# macropad_versio2.net
KiCad netlist of a schematic drawn in EAGLE
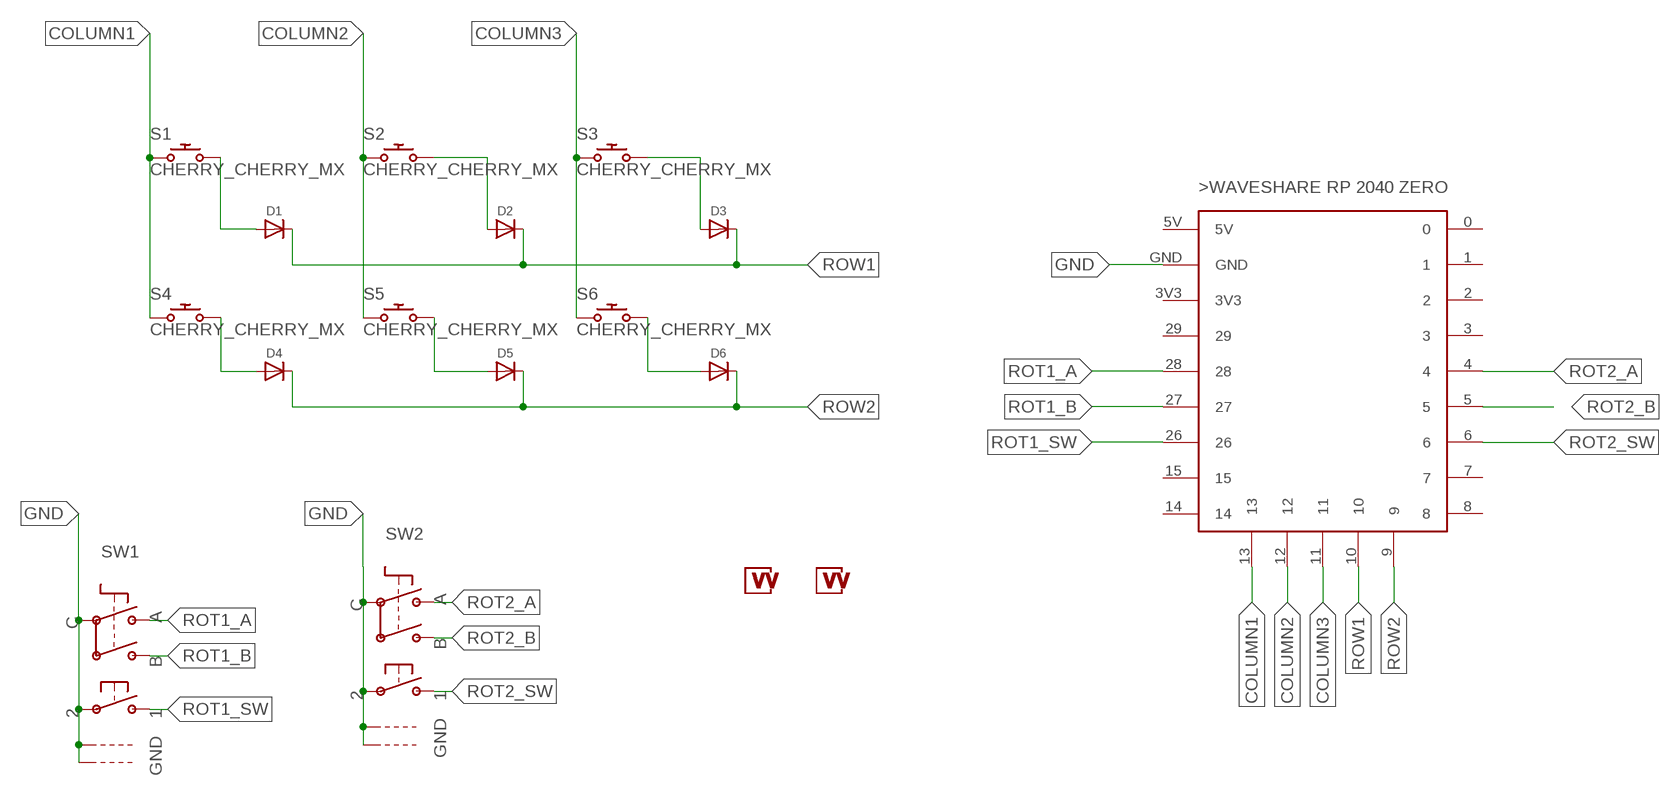
[diagram p0: schematic, sheet 1]

(export (version "E")
  (design (tool "Eeschema 10.0.6"))
  (components
    (comp (ref "D1")
      (value "ADAFRUIT-MACROPAD-2040_MICROBUILDER_DIODESOD-123")
      (footprint "eagle-import:ADAFRUIT-MACROPAD-2040_MICROBUILDER_SOD-123")
      (libsource (lib "eagle-import") (part "ADAFRUIT-MACROPAD-2040_MICROBUILDER_DIODESOD-123"))
    )
    (comp (ref "D2")
      (value "ADAFRUIT-MACROPAD-2040_MICROBUILDER_DIODESOD-123")
      (footprint "eagle-import:ADAFRUIT-MACROPAD-2040_MICROBUILDER_SOD-123")
      (libsource (lib "eagle-import") (part "ADAFRUIT-MACROPAD-2040_MICROBUILDER_DIODESOD-123"))
    )
    (comp (ref "D3")
      (value "ADAFRUIT-MACROPAD-2040_MICROBUILDER_DIODESOD-123")
      (footprint "eagle-import:ADAFRUIT-MACROPAD-2040_MICROBUILDER_SOD-123")
      (libsource (lib "eagle-import") (part "ADAFRUIT-MACROPAD-2040_MICROBUILDER_DIODESOD-123"))
    )
    (comp (ref "D4")
      (value "ADAFRUIT-MACROPAD-2040_MICROBUILDER_DIODESOD-123")
      (footprint "eagle-import:ADAFRUIT-MACROPAD-2040_MICROBUILDER_SOD-123")
      (libsource (lib "eagle-import") (part "ADAFRUIT-MACROPAD-2040_MICROBUILDER_DIODESOD-123"))
    )
    (comp (ref "D5")
      (value "ADAFRUIT-MACROPAD-2040_MICROBUILDER_DIODESOD-123")
      (footprint "eagle-import:ADAFRUIT-MACROPAD-2040_MICROBUILDER_SOD-123")
      (libsource (lib "eagle-import") (part "ADAFRUIT-MACROPAD-2040_MICROBUILDER_DIODESOD-123"))
    )
    (comp (ref "D6")
      (value "ADAFRUIT-MACROPAD-2040_MICROBUILDER_DIODESOD-123")
      (footprint "eagle-import:ADAFRUIT-MACROPAD-2040_MICROBUILDER_SOD-123")
      (libsource (lib "eagle-import") (part "ADAFRUIT-MACROPAD-2040_MICROBUILDER_DIODESOD-123"))
    )
    (comp (ref "RP2040_ZERO1")
      (value "WAVESHARE_RP2040_ZERO")
      (footprint "eagle-import:WAVESHARE-RP2040-ZERO")
      (libsource (lib "eagle-import") (part "WAVESHARE_RP2040_ZERO"))
    )
    (comp (ref "S1")
      (value "CHERRY_CHERRY_MX")
      (footprint "eagle-import:CHERRY_CHERRY_MX")
      (libsource (lib "eagle-import") (part "CHERRY_CHERRY_MX"))
    )
    (comp (ref "S2")
      (value "CHERRY_CHERRY_MX")
      (footprint "eagle-import:CHERRY_CHERRY_MX")
      (libsource (lib "eagle-import") (part "CHERRY_CHERRY_MX"))
    )
    (comp (ref "S3")
      (value "CHERRY_CHERRY_MX")
      (footprint "eagle-import:CHERRY_CHERRY_MX")
      (libsource (lib "eagle-import") (part "CHERRY_CHERRY_MX"))
    )
    (comp (ref "S4")
      (value "CHERRY_CHERRY_MX")
      (footprint "eagle-import:CHERRY_CHERRY_MX")
      (libsource (lib "eagle-import") (part "CHERRY_CHERRY_MX"))
    )
    (comp (ref "S5")
      (value "CHERRY_CHERRY_MX")
      (footprint "eagle-import:CHERRY_CHERRY_MX")
      (libsource (lib "eagle-import") (part "CHERRY_CHERRY_MX"))
    )
    (comp (ref "S6")
      (value "CHERRY_CHERRY_MX")
      (footprint "eagle-import:CHERRY_CHERRY_MX")
      (libsource (lib "eagle-import") (part "CHERRY_CHERRY_MX"))
    )
    (comp (ref "SW1")
      (value "ADAFRUIT-MACROPAD-2040_ADAFRUIT_ELECTROMECH_ENCODER_PLUS_SWITCH_BOURNS_PEC11")
      (footprint "eagle-import:ADAFRUIT-MACROPAD-2040_ADAFRUIT_ELECTROMECH_PEC11+SWITCH")
      (libsource (lib "eagle-import") (part "ADAFRUIT-MACROPAD-2040_ADAFRUIT_ELECTROMECH_ENCODER_PLUS_SWITCH_PEC11_BOURNS"))
    )
    (comp (ref "SW2")
      (value "ADAFRUIT-MACROPAD-2040_ADAFRUIT_ELECTROMECH_ENCODER_PLUS_SWITCH_BOURNS_PEC11")
      (footprint "eagle-import:ADAFRUIT-MACROPAD-2040_ADAFRUIT_ELECTROMECH_PEC11+SWITCH")
      (libsource (lib "eagle-import") (part "ADAFRUIT-MACROPAD-2040_ADAFRUIT_ELECTROMECH_ENCODER_PLUS_SWITCH_PEC11_BOURNS"))
    )
    (comp (ref "U$1")
      (value "LOGO_VV")
      (footprint "eagle-import:VV_MEDUIM")
      (libsource (lib "eagle-import") (part "LOGO_VV"))
    )
    (comp (ref "U$2")
      (value "LOGO_VV")
      (footprint "eagle-import:VV_MEDUIM")
      (libsource (lib "eagle-import") (part "LOGO_VV"))
    )
  )
  (nets
    (net (code "1") (name "COLUMN1") (class "Default")
      (node (ref "RP2040_ZERO1") (pin "13") (pinfunction "13_13") (pintype "bidirectional"))
      (node (ref "S1") (pin "S1") (pinfunction "1_S1") (pintype "passive"))
      (node (ref "S4") (pin "S1") (pinfunction "1_S1") (pintype "passive"))
    )
    (net (code "2") (name "COLUMN2") (class "Default")
      (node (ref "RP2040_ZERO1") (pin "12") (pinfunction "12_12") (pintype "bidirectional"))
      (node (ref "S2") (pin "S1") (pinfunction "1_S1") (pintype "passive"))
      (node (ref "S5") (pin "S1") (pinfunction "1_S1") (pintype "passive"))
    )
    (net (code "3") (name "COLUMN3") (class "Default")
      (node (ref "RP2040_ZERO1") (pin "11") (pinfunction "11_11") (pintype "bidirectional"))
      (node (ref "S3") (pin "S1") (pinfunction "1_S1") (pintype "passive"))
      (node (ref "S6") (pin "S1") (pinfunction "1_S1") (pintype "passive"))
    )
    (net (code "4") (name "GND") (class "Default")
      (node (ref "RP2040_ZERO1") (pin "GND") (pinfunction "GND_GND") (pintype "bidirectional"))
      (node (ref "SW1") (pin "P$2") (pinfunction "P$2_P$2") (pintype "passive"))
      (node (ref "SW1") (pin "P$C") (pinfunction "P$C_P$C") (pintype "passive"))
      (node (ref "SW1") (pin "P$GND1") (pinfunction "P$GND1_P$GND1") (pintype "passive"))
      (node (ref "SW1") (pin "P$GND2") (pinfunction "P$GND2_P$GND2") (pintype "passive"))
      (node (ref "SW2") (pin "P$2") (pinfunction "P$2_P$2") (pintype "passive"))
      (node (ref "SW2") (pin "P$C") (pinfunction "P$C_P$C") (pintype "passive"))
      (node (ref "SW2") (pin "P$GND1") (pinfunction "P$GND1_P$GND1") (pintype "passive"))
      (node (ref "SW2") (pin "P$GND2") (pinfunction "P$GND2_P$GND2") (pintype "passive"))
    )
    (net (code "5") (name "Net-(S1-2)") (class "Default")
      (node (ref "D1") (pin "A") (pinfunction "A_A") (pintype "passive"))
      (node (ref "S1") (pin "S2") (pinfunction "2_S2") (pintype "passive"))
    )
    (net (code "6") (name "Net-(S2-2)") (class "Default")
      (node (ref "D2") (pin "A") (pinfunction "A_A") (pintype "passive"))
      (node (ref "S2") (pin "S2") (pinfunction "2_S2") (pintype "passive"))
    )
    (net (code "7") (name "Net-(S3-2)") (class "Default")
      (node (ref "D3") (pin "A") (pinfunction "A_A") (pintype "passive"))
      (node (ref "S3") (pin "S2") (pinfunction "2_S2") (pintype "passive"))
    )
    (net (code "8") (name "Net-(S4-2)") (class "Default")
      (node (ref "D4") (pin "A") (pinfunction "A_A") (pintype "passive"))
      (node (ref "S4") (pin "S2") (pinfunction "2_S2") (pintype "passive"))
    )
    (net (code "9") (name "Net-(S5-2)") (class "Default")
      (node (ref "D5") (pin "A") (pinfunction "A_A") (pintype "passive"))
      (node (ref "S5") (pin "S2") (pinfunction "2_S2") (pintype "passive"))
    )
    (net (code "10") (name "Net-(S6-2)") (class "Default")
      (node (ref "D6") (pin "A") (pinfunction "A_A") (pintype "passive"))
      (node (ref "S6") (pin "S2") (pinfunction "2_S2") (pintype "passive"))
    )
    (net (code "11") (name "ROT1_A") (class "Default")
      (node (ref "RP2040_ZERO1") (pin "28") (pinfunction "28_28") (pintype "bidirectional"))
      (node (ref "SW1") (pin "P$A") (pinfunction "P$A_P$A") (pintype "passive"))
    )
    (net (code "12") (name "ROT1_B") (class "Default")
      (node (ref "RP2040_ZERO1") (pin "27") (pinfunction "27_27") (pintype "bidirectional"))
      (node (ref "SW1") (pin "P$B") (pinfunction "P$B_P$B") (pintype "passive"))
    )
    (net (code "13") (name "ROT1_SW") (class "Default")
      (node (ref "RP2040_ZERO1") (pin "26") (pinfunction "26_26") (pintype "bidirectional"))
      (node (ref "SW1") (pin "P$1") (pinfunction "P$1_P$1") (pintype "passive"))
    )
    (net (code "14") (name "ROT2_A") (class "Default")
      (node (ref "RP2040_ZERO1") (pin "4") (pinfunction "4_4") (pintype "bidirectional"))
      (node (ref "SW2") (pin "P$A") (pinfunction "P$A_P$A") (pintype "passive"))
    )
    (net (code "15") (name "ROT2_B") (class "Default")
      (node (ref "RP2040_ZERO1") (pin "5") (pinfunction "5_5") (pintype "bidirectional"))
      (node (ref "SW2") (pin "P$B") (pinfunction "P$B_P$B") (pintype "passive"))
    )
    (net (code "16") (name "ROT2_SW") (class "Default")
      (node (ref "RP2040_ZERO1") (pin "6") (pinfunction "6_6") (pintype "bidirectional"))
      (node (ref "SW2") (pin "P$1") (pinfunction "P$1_P$1") (pintype "passive"))
    )
    (net (code "17") (name "ROW1") (class "Default")
      (node (ref "D1") (pin "C") (pinfunction "C_C") (pintype "passive"))
      (node (ref "D2") (pin "C") (pinfunction "C_C") (pintype "passive"))
      (node (ref "D3") (pin "C") (pinfunction "C_C") (pintype "passive"))
      (node (ref "RP2040_ZERO1") (pin "10") (pinfunction "10_10") (pintype "bidirectional"))
    )
    (net (code "18") (name "ROW2") (class "Default")
      (node (ref "D4") (pin "C") (pinfunction "C_C") (pintype "passive"))
      (node (ref "D5") (pin "C") (pinfunction "C_C") (pintype "passive"))
      (node (ref "D6") (pin "C") (pinfunction "C_C") (pintype "passive"))
      (node (ref "RP2040_ZERO1") (pin "9") (pinfunction "9_9") (pintype "bidirectional"))
    )
    (net (code "19") (name "unconnected-(RP2040_ZERO1-Pad0)") (class "Default")
      (node (ref "RP2040_ZERO1") (pin "0") (pinfunction "0_0") (pintype "bidirectional"))
    )
    (net (code "20") (name "unconnected-(RP2040_ZERO1-Pad1)") (class "Default")
      (node (ref "RP2040_ZERO1") (pin "1") (pinfunction "1_1") (pintype "bidirectional"))
    )
    (net (code "21") (name "unconnected-(RP2040_ZERO1-Pad2)") (class "Default")
      (node (ref "RP2040_ZERO1") (pin "2") (pinfunction "2_2") (pintype "bidirectional"))
    )
    (net (code "22") (name "unconnected-(RP2040_ZERO1-Pad3)") (class "Default")
      (node (ref "RP2040_ZERO1") (pin "3") (pinfunction "3_3") (pintype "bidirectional"))
    )
    (net (code "23") (name "unconnected-(RP2040_ZERO1-Pad3V3)") (class "Default")
      (node (ref "RP2040_ZERO1") (pin "3V3") (pinfunction "3V3_3V3") (pintype "bidirectional"))
    )
    (net (code "24") (name "unconnected-(RP2040_ZERO1-Pad5V)") (class "Default")
      (node (ref "RP2040_ZERO1") (pin "5V") (pinfunction "5V_5V") (pintype "bidirectional"))
    )
    (net (code "25") (name "unconnected-(RP2040_ZERO1-Pad7)") (class "Default")
      (node (ref "RP2040_ZERO1") (pin "7") (pinfunction "7_7") (pintype "bidirectional"))
    )
    (net (code "26") (name "unconnected-(RP2040_ZERO1-Pad8)") (class "Default")
      (node (ref "RP2040_ZERO1") (pin "8") (pinfunction "8_8") (pintype "bidirectional"))
    )
    (net (code "27") (name "unconnected-(RP2040_ZERO1-Pad14)") (class "Default")
      (node (ref "RP2040_ZERO1") (pin "14") (pinfunction "14_14") (pintype "bidirectional"))
    )
    (net (code "28") (name "unconnected-(RP2040_ZERO1-Pad15)") (class "Default")
      (node (ref "RP2040_ZERO1") (pin "15") (pinfunction "15_15") (pintype "bidirectional"))
    )
    (net (code "29") (name "unconnected-(RP2040_ZERO1-Pad29)") (class "Default")
      (node (ref "RP2040_ZERO1") (pin "29") (pinfunction "29_29") (pintype "bidirectional"))
    )
  )
)
